# Connector.net
KiCad netlist of a schematic drawn in Altium Designer
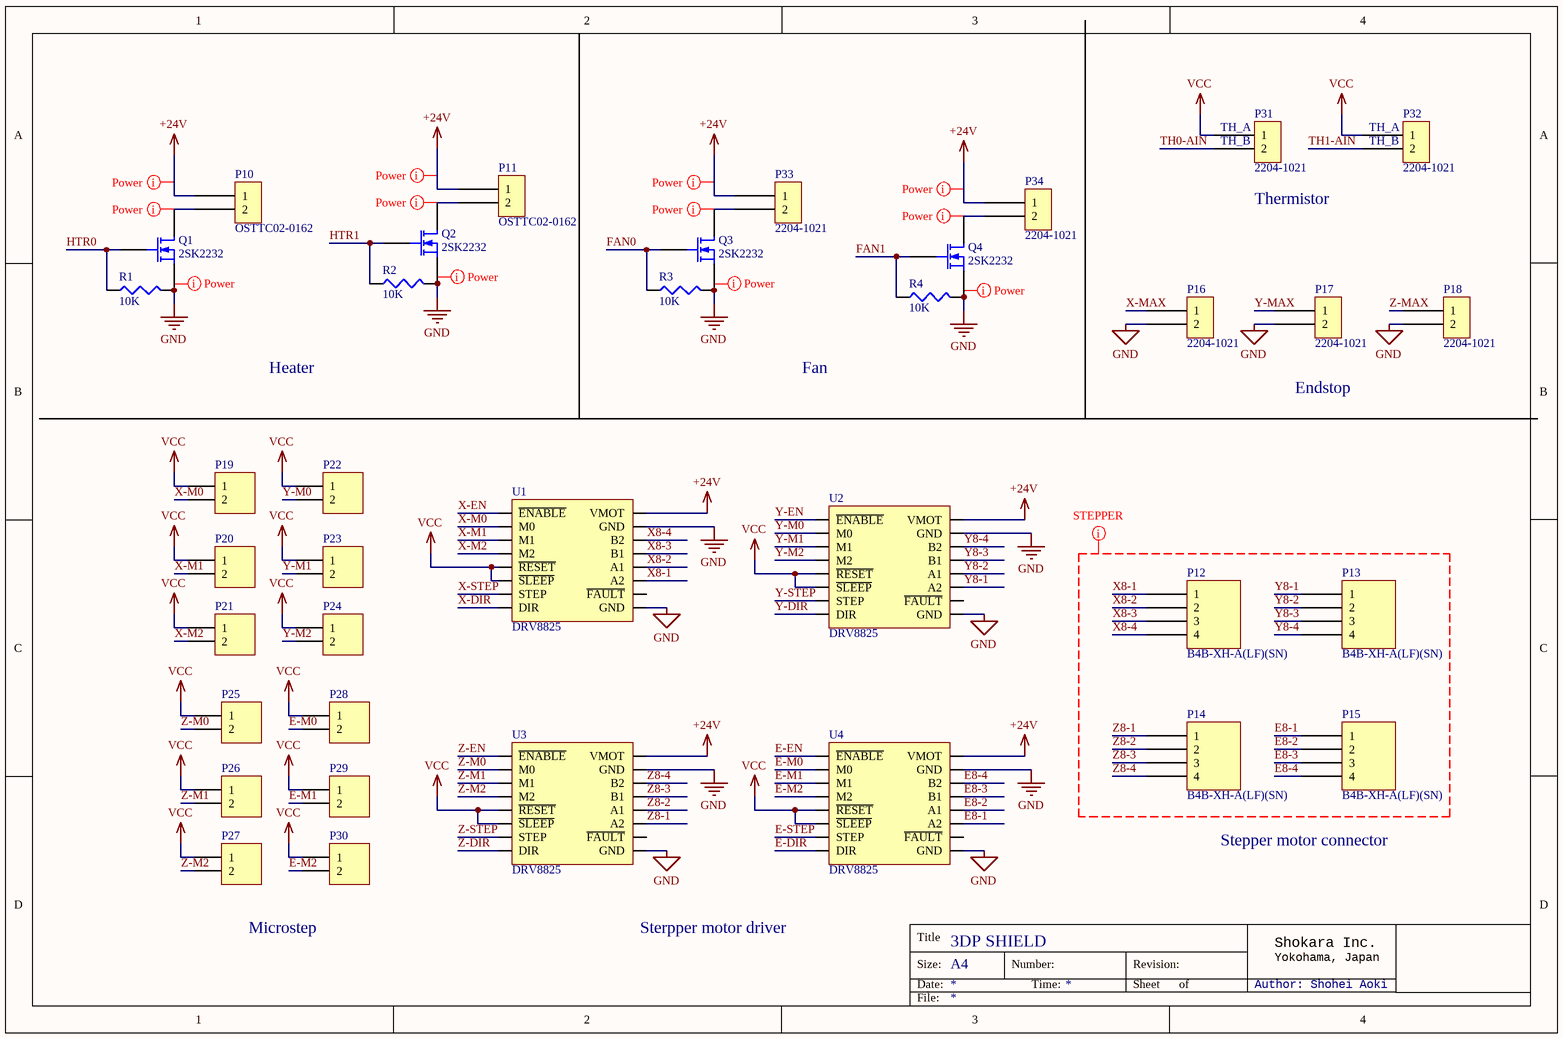
[diagram p0: Connector.SchDoc]

(export (version "E")
  (design (tool "Eeschema 10.0.6"))
  (components
    (comp (ref "P10")
      (value "OSTTC02-0162")
      (footprint "OSTTC02-0162")
      (libsource (lib "3dprinter_shield") (part "TERMINAL_BLOCK_1X2"))
    )
    (comp (ref "P11")
      (value "OSTTC02-0162")
      (footprint "OSTTC02-0162")
      (libsource (lib "3dprinter_shield") (part "TERMINAL_BLOCK_1X2"))
    )
    (comp (ref "P12")
      (value "B4B-XH-A(LF)(SN)")
      (footprint "B4B-XH-A")
      (libsource (lib "3dprinter_shield") (part "XH_CONNECTOR_1X4"))
    )
    (comp (ref "P13")
      (value "B4B-XH-A(LF)(SN)")
      (footprint "B4B-XH-A")
      (libsource (lib "3dprinter_shield") (part "XH_CONNECTOR_1X4"))
    )
    (comp (ref "P14")
      (value "B4B-XH-A(LF)(SN)")
      (footprint "B4B-XH-A")
      (libsource (lib "3dprinter_shield") (part "XH_CONNECTOR_1X4"))
    )
    (comp (ref "P15")
      (value "B4B-XH-A(LF)(SN)")
      (footprint "B4B-XH-A")
      (libsource (lib "3dprinter_shield") (part "XH_CONNECTOR_1X4"))
    )
    (comp (ref "P16")
      (value "2204-1021")
      (footprint "MOLEX_2204_1021")
      (libsource (lib "3dprinter_shield") (part "MOLEX_1X2_HEADER"))
    )
    (comp (ref "P17")
      (value "2204-1021")
      (footprint "MOLEX_2204_1021")
      (libsource (lib "3dprinter_shield") (part "MOLEX_1X2_HEADER"))
    )
    (comp (ref "P18")
      (value "2204-1021")
      (footprint "MOLEX_2204_1021")
      (libsource (lib "3dprinter_shield") (part "MOLEX_1X2_HEADER"))
    )
    (comp (ref "P19")
      (value "Header 2")
      (footprint "HDR1X2")
      (description "Header, 2-Pin")
      (fields (field (name "PUBLISHER") "Altium Limited"))
      (libsource (lib "Miscellaneous Connectors") (part "Header 2"))
    )
    (comp (ref "P20")
      (value "Header 2")
      (footprint "HDR1X2")
      (description "Header, 2-Pin")
      (fields (field (name "PUBLISHER") "Altium Limited"))
      (libsource (lib "Miscellaneous Connectors") (part "Header 2"))
    )
    (comp (ref "P21")
      (value "Header 2")
      (footprint "HDR1X2")
      (description "Header, 2-Pin")
      (fields (field (name "PUBLISHER") "Altium Limited"))
      (libsource (lib "Miscellaneous Connectors") (part "Header 2"))
    )
    (comp (ref "P22")
      (value "Header 2")
      (footprint "HDR1X2")
      (description "Header, 2-Pin")
      (fields (field (name "PUBLISHER") "Altium Limited"))
      (libsource (lib "Miscellaneous Connectors") (part "Header 2"))
    )
    (comp (ref "P23")
      (value "Header 2")
      (footprint "HDR1X2")
      (description "Header, 2-Pin")
      (fields (field (name "PUBLISHER") "Altium Limited"))
      (libsource (lib "Miscellaneous Connectors") (part "Header 2"))
    )
    (comp (ref "P24")
      (value "Header 2")
      (footprint "HDR1X2")
      (description "Header, 2-Pin")
      (fields (field (name "PUBLISHER") "Altium Limited"))
      (libsource (lib "Miscellaneous Connectors") (part "Header 2"))
    )
    (comp (ref "P25")
      (value "Header 2")
      (footprint "HDR1X2")
      (description "Header, 2-Pin")
      (fields (field (name "PUBLISHER") "Altium Limited"))
      (libsource (lib "Miscellaneous Connectors") (part "Header 2"))
    )
    (comp (ref "P26")
      (value "Header 2")
      (footprint "HDR1X2")
      (description "Header, 2-Pin")
      (fields (field (name "PUBLISHER") "Altium Limited"))
      (libsource (lib "Miscellaneous Connectors") (part "Header 2"))
    )
    (comp (ref "P27")
      (value "Header 2")
      (footprint "HDR1X2")
      (description "Header, 2-Pin")
      (fields (field (name "PUBLISHER") "Altium Limited"))
      (libsource (lib "Miscellaneous Connectors") (part "Header 2"))
    )
    (comp (ref "P28")
      (value "Header 2")
      (footprint "HDR1X2")
      (description "Header, 2-Pin")
      (fields (field (name "PUBLISHER") "Altium Limited"))
      (libsource (lib "Miscellaneous Connectors") (part "Header 2"))
    )
    (comp (ref "P29")
      (value "Header 2")
      (footprint "HDR1X2")
      (description "Header, 2-Pin")
      (fields (field (name "PUBLISHER") "Altium Limited"))
      (libsource (lib "Miscellaneous Connectors") (part "Header 2"))
    )
    (comp (ref "P30")
      (value "Header 2")
      (footprint "HDR1X2")
      (description "Header, 2-Pin")
      (fields (field (name "PUBLISHER") "Altium Limited"))
      (libsource (lib "Miscellaneous Connectors") (part "Header 2"))
    )
    (comp (ref "P31")
      (value "2204-1021")
      (footprint "MOLEX_2204_1021")
      (libsource (lib "3dprinter_shield") (part "MOLEX_1X2_HEADER"))
    )
    (comp (ref "P32")
      (value "2204-1021")
      (footprint "MOLEX_2204_1021")
      (libsource (lib "3dprinter_shield") (part "MOLEX_1X2_HEADER"))
    )
    (comp (ref "P33")
      (value "2204-1021")
      (footprint "MOLEX_2204_1021")
      (libsource (lib "3dprinter_shield") (part "MOLEX_1X2_HEADER"))
    )
    (comp (ref "P34")
      (value "2204-1021")
      (footprint "MOLEX_2204_1021")
      (libsource (lib "3dprinter_shield") (part "MOLEX_1X2_HEADER"))
    )
    (comp (ref "Q1")
      (value "2SK2232")
      (footprint "2SK2232")
      (libsource (lib "3dprinter_shield") (part "2SK2232"))
    )
    (comp (ref "Q2")
      (value "2SK2232")
      (footprint "2SK2232")
      (libsource (lib "3dprinter_shield") (part "2SK2232"))
    )
    (comp (ref "Q3")
      (value "2SK2232")
      (footprint "2SK2232")
      (libsource (lib "3dprinter_shield") (part "2SK2232"))
    )
    (comp (ref "Q4")
      (value "2SK2232")
      (footprint "2SK2232")
      (libsource (lib "3dprinter_shield") (part "2SK2232"))
    )
    (comp (ref "R1")
      (value "10K")
      (footprint "J1-0603")
      (description "Resistor")
      (fields (field (name "PUBLISHER") "Altium Limited"))
      (libsource (lib "Miscellaneous Devices") (part "Res3"))
    )
    (comp (ref "R2")
      (value "10K")
      (footprint "J1-0603")
      (description "Resistor")
      (fields (field (name "PUBLISHER") "Altium Limited"))
      (libsource (lib "Miscellaneous Devices") (part "Res3"))
    )
    (comp (ref "R3")
      (value "10K")
      (footprint "J1-0603")
      (description "Resistor")
      (fields (field (name "PUBLISHER") "Altium Limited"))
      (libsource (lib "Miscellaneous Devices") (part "Res3"))
    )
    (comp (ref "R4")
      (value "10K")
      (footprint "J1-0603")
      (description "Resistor")
      (fields (field (name "PUBLISHER") "Altium Limited"))
      (libsource (lib "Miscellaneous Devices") (part "Res3"))
    )
    (comp (ref "U1")
      (value "DRV8825")
      (footprint "DRV8825")
      (libsource (lib "3dprinter_shield") (part "DRV8825"))
    )
    (comp (ref "U2")
      (value "DRV8825")
      (footprint "DRV8825")
      (libsource (lib "3dprinter_shield") (part "DRV8825"))
    )
    (comp (ref "U3")
      (value "DRV8825")
      (footprint "DRV8825")
      (libsource (lib "3dprinter_shield") (part "DRV8825"))
    )
    (comp (ref "U4")
      (value "DRV8825")
      (footprint "DRV8825")
      (libsource (lib "3dprinter_shield") (part "DRV8825"))
    )
  )
  (nets
    (net (code "1") (name "+24V") (class "Default")
      (node (ref "P10") (pin "1") (pinfunction "1_1") (pintype "passive"))
      (node (ref "P11") (pin "1") (pinfunction "1_1") (pintype "passive"))
      (node (ref "P33") (pin "1") (pinfunction "1_1") (pintype "passive"))
      (node (ref "P34") (pin "1") (pinfunction "1_1") (pintype "passive"))
      (node (ref "U1") (pin "VMOT") (pinfunction "VMOT_VMOT") (pintype "passive"))
      (node (ref "U2") (pin "VMOT") (pinfunction "VMOT_VMOT") (pintype "passive"))
      (node (ref "U3") (pin "VMOT") (pinfunction "VMOT_VMOT") (pintype "passive"))
      (node (ref "U4") (pin "VMOT") (pinfunction "VMOT_VMOT") (pintype "passive"))
    )
    (net (code "2") (name "/E-DIR") (class "Default")
      (node (ref "U4") (pin "DIR") (pinfunction "DIR_DIR") (pintype "passive"))
    )
    (net (code "3") (name "/E-EN") (class "Default")
      (node (ref "U4") (pin "ENABLE") (pinfunction "~{ENABLE}_ENABLE") (pintype "passive"))
    )
    (net (code "4") (name "/E-M0") (class "Default")
      (node (ref "P28") (pin "2") (pinfunction "2_2") (pintype "passive"))
      (node (ref "U4") (pin "M0") (pinfunction "M0_M0") (pintype "passive"))
    )
    (net (code "5") (name "/E-M1") (class "Default")
      (node (ref "P29") (pin "2") (pinfunction "2_2") (pintype "passive"))
      (node (ref "U4") (pin "M1") (pinfunction "M1_M1") (pintype "passive"))
    )
    (net (code "6") (name "/E-M2") (class "Default")
      (node (ref "P30") (pin "2") (pinfunction "2_2") (pintype "passive"))
      (node (ref "U4") (pin "M2") (pinfunction "M2_M2") (pintype "passive"))
    )
    (net (code "7") (name "/E-STEP") (class "Default")
      (node (ref "U4") (pin "STEP") (pinfunction "STEP_STEP") (pintype "passive"))
    )
    (net (code "8") (name "/E8-1") (class "Default")
      (node (ref "P15") (pin "1") (pinfunction "1_1") (pintype "passive"))
      (node (ref "U4") (pin "A2") (pinfunction "A2_A2") (pintype "passive"))
    )
    (net (code "9") (name "/E8-2") (class "Default")
      (node (ref "P15") (pin "2") (pinfunction "2_2") (pintype "passive"))
      (node (ref "U4") (pin "A1") (pinfunction "A1_A1") (pintype "passive"))
    )
    (net (code "10") (name "/E8-3") (class "Default")
      (node (ref "P15") (pin "3") (pinfunction "3_3") (pintype "passive"))
      (node (ref "U4") (pin "B1") (pinfunction "B1_B1") (pintype "passive"))
    )
    (net (code "11") (name "/E8-4") (class "Default")
      (node (ref "P15") (pin "4") (pinfunction "4_4") (pintype "passive"))
      (node (ref "U4") (pin "B2") (pinfunction "B2_B2") (pintype "passive"))
    )
    (net (code "12") (name "/FAN0") (class "Default")
      (node (ref "Q3") (pin "G") (pinfunction "G_G") (pintype "passive"))
      (node (ref "R3") (pin "1") (pinfunction "1_1") (pintype "passive"))
    )
    (net (code "13") (name "/FAN1") (class "Default")
      (node (ref "Q4") (pin "G") (pinfunction "G_G") (pintype "passive"))
      (node (ref "R4") (pin "1") (pinfunction "1_1") (pintype "passive"))
    )
    (net (code "14") (name "/HTR0") (class "Default")
      (node (ref "Q1") (pin "G") (pinfunction "G_G") (pintype "passive"))
      (node (ref "R1") (pin "1") (pinfunction "1_1") (pintype "passive"))
    )
    (net (code "15") (name "/HTR1") (class "Default")
      (node (ref "Q2") (pin "G") (pinfunction "G_G") (pintype "passive"))
      (node (ref "R2") (pin "1") (pinfunction "1_1") (pintype "passive"))
    )
    (net (code "16") (name "/TH0-AIN") (class "Default")
      (node (ref "P31") (pin "2") (pinfunction "2_2") (pintype "passive"))
    )
    (net (code "17") (name "/TH1-AIN") (class "Default")
      (node (ref "P32") (pin "2") (pinfunction "2_2") (pintype "passive"))
    )
    (net (code "18") (name "/X-DIR") (class "Default")
      (node (ref "U1") (pin "DIR") (pinfunction "DIR_DIR") (pintype "passive"))
    )
    (net (code "19") (name "/X-EN") (class "Default")
      (node (ref "U1") (pin "ENABLE") (pinfunction "~{ENABLE}_ENABLE") (pintype "passive"))
    )
    (net (code "20") (name "/X-M0") (class "Default")
      (node (ref "P19") (pin "2") (pinfunction "2_2") (pintype "passive"))
      (node (ref "U1") (pin "M0") (pinfunction "M0_M0") (pintype "passive"))
    )
    (net (code "21") (name "/X-M1") (class "Default")
      (node (ref "P20") (pin "2") (pinfunction "2_2") (pintype "passive"))
      (node (ref "U1") (pin "M1") (pinfunction "M1_M1") (pintype "passive"))
    )
    (net (code "22") (name "/X-M2") (class "Default")
      (node (ref "P21") (pin "2") (pinfunction "2_2") (pintype "passive"))
      (node (ref "U1") (pin "M2") (pinfunction "M2_M2") (pintype "passive"))
    )
    (net (code "23") (name "/X-MAX") (class "Default")
      (node (ref "P16") (pin "1") (pinfunction "1_1") (pintype "passive"))
    )
    (net (code "24") (name "/X-STEP") (class "Default")
      (node (ref "U1") (pin "STEP") (pinfunction "STEP_STEP") (pintype "passive"))
    )
    (net (code "25") (name "/X8-1") (class "Default")
      (node (ref "P12") (pin "1") (pinfunction "1_1") (pintype "passive"))
      (node (ref "U1") (pin "A2") (pinfunction "A2_A2") (pintype "passive"))
    )
    (net (code "26") (name "/X8-2") (class "Default")
      (node (ref "P12") (pin "2") (pinfunction "2_2") (pintype "passive"))
      (node (ref "U1") (pin "A1") (pinfunction "A1_A1") (pintype "passive"))
    )
    (net (code "27") (name "/X8-3") (class "Default")
      (node (ref "P12") (pin "3") (pinfunction "3_3") (pintype "passive"))
      (node (ref "U1") (pin "B1") (pinfunction "B1_B1") (pintype "passive"))
    )
    (net (code "28") (name "/X8-4") (class "Default")
      (node (ref "P12") (pin "4") (pinfunction "4_4") (pintype "passive"))
      (node (ref "U1") (pin "B2") (pinfunction "B2_B2") (pintype "passive"))
    )
    (net (code "29") (name "/Y-DIR") (class "Default")
      (node (ref "U2") (pin "DIR") (pinfunction "DIR_DIR") (pintype "passive"))
    )
    (net (code "30") (name "/Y-EN") (class "Default")
      (node (ref "U2") (pin "ENABLE") (pinfunction "~{ENABLE}_ENABLE") (pintype "passive"))
    )
    (net (code "31") (name "/Y-M0") (class "Default")
      (node (ref "P22") (pin "2") (pinfunction "2_2") (pintype "passive"))
      (node (ref "U2") (pin "M0") (pinfunction "M0_M0") (pintype "passive"))
    )
    (net (code "32") (name "/Y-M1") (class "Default")
      (node (ref "P23") (pin "2") (pinfunction "2_2") (pintype "passive"))
      (node (ref "U2") (pin "M1") (pinfunction "M1_M1") (pintype "passive"))
    )
    (net (code "33") (name "/Y-M2") (class "Default")
      (node (ref "P24") (pin "2") (pinfunction "2_2") (pintype "passive"))
      (node (ref "U2") (pin "M2") (pinfunction "M2_M2") (pintype "passive"))
    )
    (net (code "34") (name "/Y-MAX") (class "Default")
      (node (ref "P17") (pin "1") (pinfunction "1_1") (pintype "passive"))
    )
    (net (code "35") (name "/Y-STEP") (class "Default")
      (node (ref "U2") (pin "STEP") (pinfunction "STEP_STEP") (pintype "passive"))
    )
    (net (code "36") (name "/Y8-1") (class "Default")
      (node (ref "P13") (pin "1") (pinfunction "1_1") (pintype "passive"))
      (node (ref "U2") (pin "A2") (pinfunction "A2_A2") (pintype "passive"))
    )
    (net (code "37") (name "/Y8-2") (class "Default")
      (node (ref "P13") (pin "2") (pinfunction "2_2") (pintype "passive"))
      (node (ref "U2") (pin "A1") (pinfunction "A1_A1") (pintype "passive"))
    )
    (net (code "38") (name "/Y8-3") (class "Default")
      (node (ref "P13") (pin "3") (pinfunction "3_3") (pintype "passive"))
      (node (ref "U2") (pin "B1") (pinfunction "B1_B1") (pintype "passive"))
    )
    (net (code "39") (name "/Y8-4") (class "Default")
      (node (ref "P13") (pin "4") (pinfunction "4_4") (pintype "passive"))
      (node (ref "U2") (pin "B2") (pinfunction "B2_B2") (pintype "passive"))
    )
    (net (code "40") (name "/Z-DIR") (class "Default")
      (node (ref "U3") (pin "DIR") (pinfunction "DIR_DIR") (pintype "passive"))
    )
    (net (code "41") (name "/Z-EN") (class "Default")
      (node (ref "U3") (pin "ENABLE") (pinfunction "~{ENABLE}_ENABLE") (pintype "passive"))
    )
    (net (code "42") (name "/Z-M0") (class "Default")
      (node (ref "P25") (pin "2") (pinfunction "2_2") (pintype "passive"))
      (node (ref "U3") (pin "M0") (pinfunction "M0_M0") (pintype "passive"))
    )
    (net (code "43") (name "/Z-M1") (class "Default")
      (node (ref "P26") (pin "2") (pinfunction "2_2") (pintype "passive"))
      (node (ref "U3") (pin "M1") (pinfunction "M1_M1") (pintype "passive"))
    )
    (net (code "44") (name "/Z-M2") (class "Default")
      (node (ref "P27") (pin "2") (pinfunction "2_2") (pintype "passive"))
      (node (ref "U3") (pin "M2") (pinfunction "M2_M2") (pintype "passive"))
    )
    (net (code "45") (name "/Z-MAX") (class "Default")
      (node (ref "P18") (pin "1") (pinfunction "1_1") (pintype "passive"))
    )
    (net (code "46") (name "/Z-STEP") (class "Default")
      (node (ref "U3") (pin "STEP") (pinfunction "STEP_STEP") (pintype "passive"))
    )
    (net (code "47") (name "/Z8-1") (class "Default")
      (node (ref "P14") (pin "1") (pinfunction "1_1") (pintype "passive"))
      (node (ref "U3") (pin "A2") (pinfunction "A2_A2") (pintype "passive"))
    )
    (net (code "48") (name "/Z8-2") (class "Default")
      (node (ref "P14") (pin "2") (pinfunction "2_2") (pintype "passive"))
      (node (ref "U3") (pin "A1") (pinfunction "A1_A1") (pintype "passive"))
    )
    (net (code "49") (name "/Z8-3") (class "Default")
      (node (ref "P14") (pin "3") (pinfunction "3_3") (pintype "passive"))
      (node (ref "U3") (pin "B1") (pinfunction "B1_B1") (pintype "passive"))
    )
    (net (code "50") (name "/Z8-4") (class "Default")
      (node (ref "P14") (pin "4") (pinfunction "4_4") (pintype "passive"))
      (node (ref "U3") (pin "B2") (pinfunction "B2_B2") (pintype "passive"))
    )
    (net (code "51") (name "GND") (class "Default")
      (node (ref "P16") (pin "2") (pinfunction "2_2") (pintype "passive"))
      (node (ref "P17") (pin "2") (pinfunction "2_2") (pintype "passive"))
      (node (ref "P18") (pin "2") (pinfunction "2_2") (pintype "passive"))
      (node (ref "Q1") (pin "S") (pinfunction "S_S") (pintype "passive"))
      (node (ref "Q2") (pin "S") (pinfunction "S_S") (pintype "passive"))
      (node (ref "Q3") (pin "S") (pinfunction "S_S") (pintype "passive"))
      (node (ref "Q4") (pin "S") (pinfunction "S_S") (pintype "passive"))
      (node (ref "R1") (pin "2") (pinfunction "2_2") (pintype "passive"))
      (node (ref "R2") (pin "2") (pinfunction "2_2") (pintype "passive"))
      (node (ref "R3") (pin "2") (pinfunction "2_2") (pintype "passive"))
      (node (ref "R4") (pin "2") (pinfunction "2_2") (pintype "passive"))
      (node (ref "U1") (pin "GND") (pinfunction "GND_GND") (pintype "passive"))
      (node (ref "U2") (pin "GND") (pinfunction "GND_GND") (pintype "passive"))
      (node (ref "U3") (pin "GND") (pinfunction "GND_GND") (pintype "passive"))
      (node (ref "U4") (pin "GND") (pinfunction "GND_GND") (pintype "passive"))
    )
    (net (code "52") (name "Net-(P10-Pad2)") (class "Default")
      (node (ref "P10") (pin "2") (pinfunction "2_2") (pintype "passive"))
      (node (ref "Q1") (pin "D") (pinfunction "D_D") (pintype "passive"))
    )
    (net (code "53") (name "Net-(P11-Pad2)") (class "Default")
      (node (ref "P11") (pin "2") (pinfunction "2_2") (pintype "passive"))
      (node (ref "Q2") (pin "D") (pinfunction "D_D") (pintype "passive"))
    )
    (net (code "54") (name "Net-(P33-Pad2)") (class "Default")
      (node (ref "P33") (pin "2") (pinfunction "2_2") (pintype "passive"))
      (node (ref "Q3") (pin "D") (pinfunction "D_D") (pintype "passive"))
    )
    (net (code "55") (name "Net-(P34-Pad2)") (class "Default")
      (node (ref "P34") (pin "2") (pinfunction "2_2") (pintype "passive"))
      (node (ref "Q4") (pin "D") (pinfunction "D_D") (pintype "passive"))
    )
    (net (code "56") (name "VCC") (class "Default")
      (node (ref "P19") (pin "1") (pinfunction "1_1") (pintype "passive"))
      (node (ref "P20") (pin "1") (pinfunction "1_1") (pintype "passive"))
      (node (ref "P21") (pin "1") (pinfunction "1_1") (pintype "passive"))
      (node (ref "P22") (pin "1") (pinfunction "1_1") (pintype "passive"))
      (node (ref "P23") (pin "1") (pinfunction "1_1") (pintype "passive"))
      (node (ref "P24") (pin "1") (pinfunction "1_1") (pintype "passive"))
      (node (ref "P25") (pin "1") (pinfunction "1_1") (pintype "passive"))
      (node (ref "P26") (pin "1") (pinfunction "1_1") (pintype "passive"))
      (node (ref "P27") (pin "1") (pinfunction "1_1") (pintype "passive"))
      (node (ref "P28") (pin "1") (pinfunction "1_1") (pintype "passive"))
      (node (ref "P29") (pin "1") (pinfunction "1_1") (pintype "passive"))
      (node (ref "P30") (pin "1") (pinfunction "1_1") (pintype "passive"))
      (node (ref "P31") (pin "1") (pinfunction "1_1") (pintype "passive"))
      (node (ref "P32") (pin "1") (pinfunction "1_1") (pintype "passive"))
      (node (ref "U1") (pin "RESET") (pinfunction "~{RESET}_RESET") (pintype "passive"))
      (node (ref "U1") (pin "SLEEP") (pinfunction "~{SLEEP}_SLEEP") (pintype "passive"))
      (node (ref "U2") (pin "RESET") (pinfunction "~{RESET}_RESET") (pintype "passive"))
      (node (ref "U2") (pin "SLEEP") (pinfunction "~{SLEEP}_SLEEP") (pintype "passive"))
      (node (ref "U3") (pin "RESET") (pinfunction "~{RESET}_RESET") (pintype "passive"))
      (node (ref "U3") (pin "SLEEP") (pinfunction "~{SLEEP}_SLEEP") (pintype "passive"))
      (node (ref "U4") (pin "RESET") (pinfunction "~{RESET}_RESET") (pintype "passive"))
      (node (ref "U4") (pin "SLEEP") (pinfunction "~{SLEEP}_SLEEP") (pintype "passive"))
    )
    (net (code "57") (name "unconnected-(U1-~{FAULT}-PadFAULT)") (class "Default")
      (node (ref "U1") (pin "FAULT") (pinfunction "~{FAULT}_FAULT") (pintype "passive"))
    )
    (net (code "58") (name "unconnected-(U2-~{FAULT}-PadFAULT)") (class "Default")
      (node (ref "U2") (pin "FAULT") (pinfunction "~{FAULT}_FAULT") (pintype "passive"))
    )
    (net (code "59") (name "unconnected-(U3-~{FAULT}-PadFAULT)") (class "Default")
      (node (ref "U3") (pin "FAULT") (pinfunction "~{FAULT}_FAULT") (pintype "passive"))
    )
    (net (code "60") (name "unconnected-(U4-~{FAULT}-PadFAULT)") (class "Default")
      (node (ref "U4") (pin "FAULT") (pinfunction "~{FAULT}_FAULT") (pintype "passive"))
    )
  )
)
